# root.net
KiCad netlist of a schematic drawn in Altium Designer
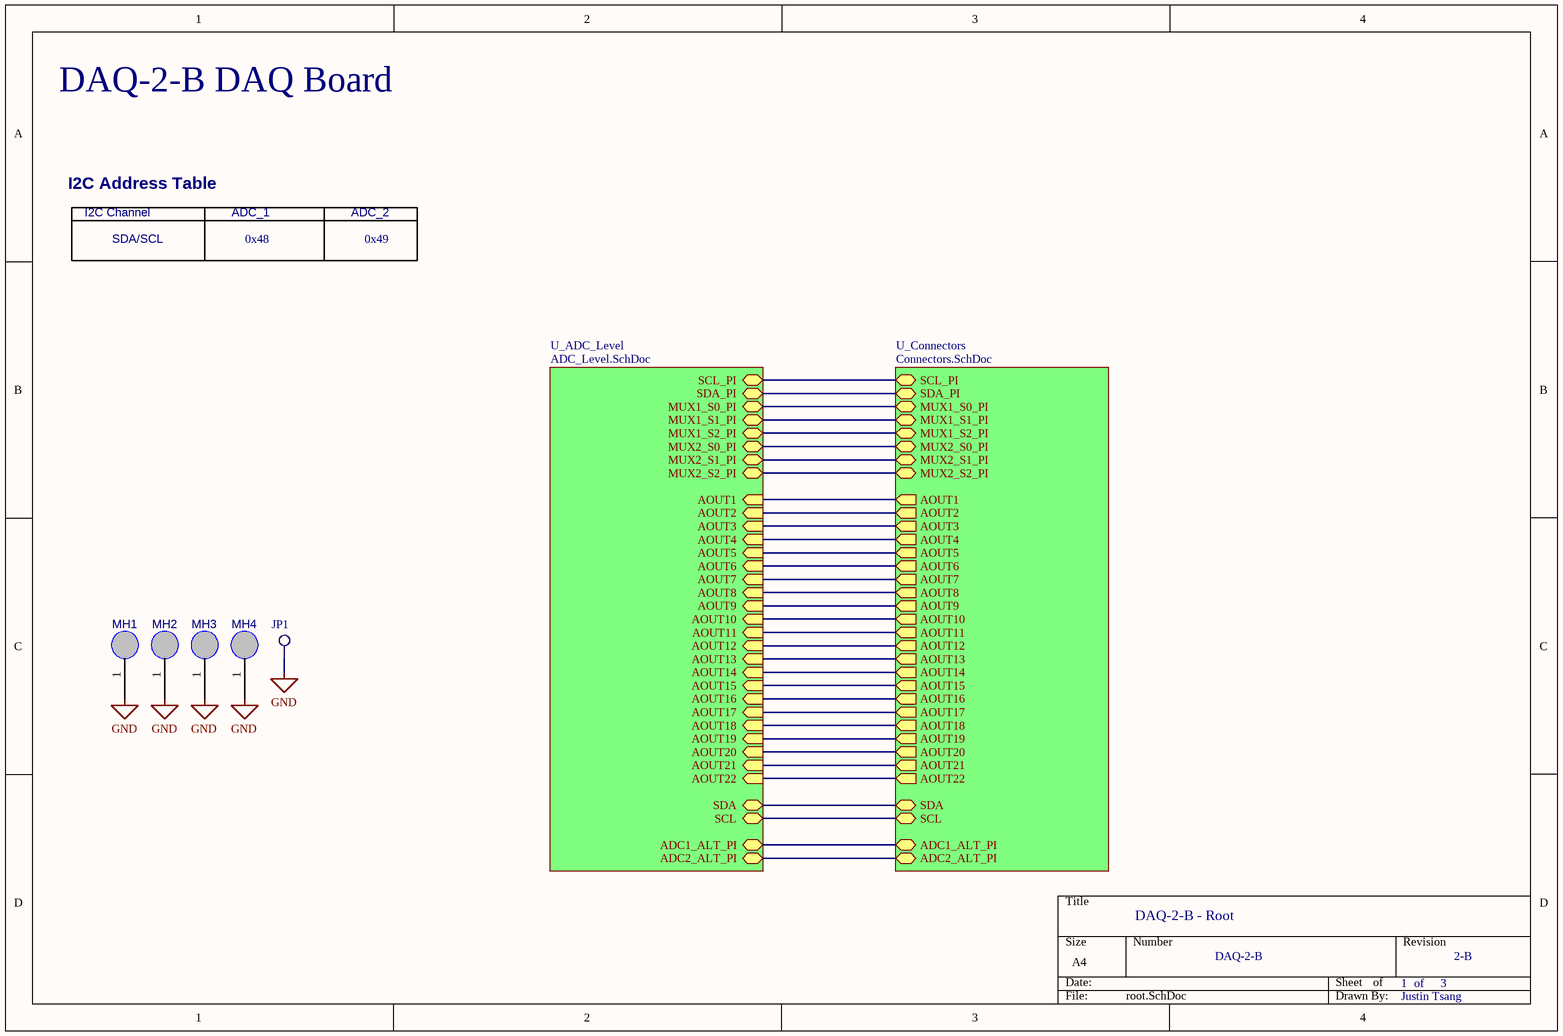
[diagram p0: root.SchDoc]

(export (version "E")
  (design (tool "Eeschema 10.0.6"))
  (components
    (comp (ref "JP1")
      (value "Testpoint2")
      (footprint "TP2")
      (description "Single layer pad TP")
      (libsource (lib "Misc") (part "Testpoint2"))
    )
    (comp (ref "MH1")
      (value "MountingHole")
      (footprint "New_Parts:MH2.7MM")
      (description "Mounting hole, 2.7mm")
      (libsource (lib "New_Parts") (part "MH2.75mm"))
    )
    (comp (ref "MH2")
      (value "MountingHole")
      (footprint "New_Parts:MH2.7MM")
      (description "Mounting hole, 2.7mm")
      (libsource (lib "New_Parts") (part "MH2.75mm"))
    )
    (comp (ref "MH3")
      (value "MountingHole")
      (footprint "New_Parts:MH2.7MM")
      (description "Mounting hole, 2.7mm")
      (libsource (lib "New_Parts") (part "MH2.75mm"))
    )
    (comp (ref "MH4")
      (value "MountingHole")
      (footprint "New_Parts:MH2.7MM")
      (description "Mounting hole, 2.7mm")
      (libsource (lib "New_Parts") (part "MH2.75mm"))
    )
  )
  (nets
    (net (code "35") (name "GND") (class "Default")
      (node (ref "JP1") (pin "1") (pinfunction "1_1") (pintype "passive"))
      (node (ref "MH1") (pin "1") (pintype "passive"))
      (node (ref "MH2") (pin "1") (pintype "passive"))
      (node (ref "MH3") (pin "1") (pintype "passive"))
      (node (ref "MH4") (pin "1") (pintype "passive"))
    )
  )
)
